# TRF_PCB_021726.net
KiCad netlist of a schematic drawn in EAGLE
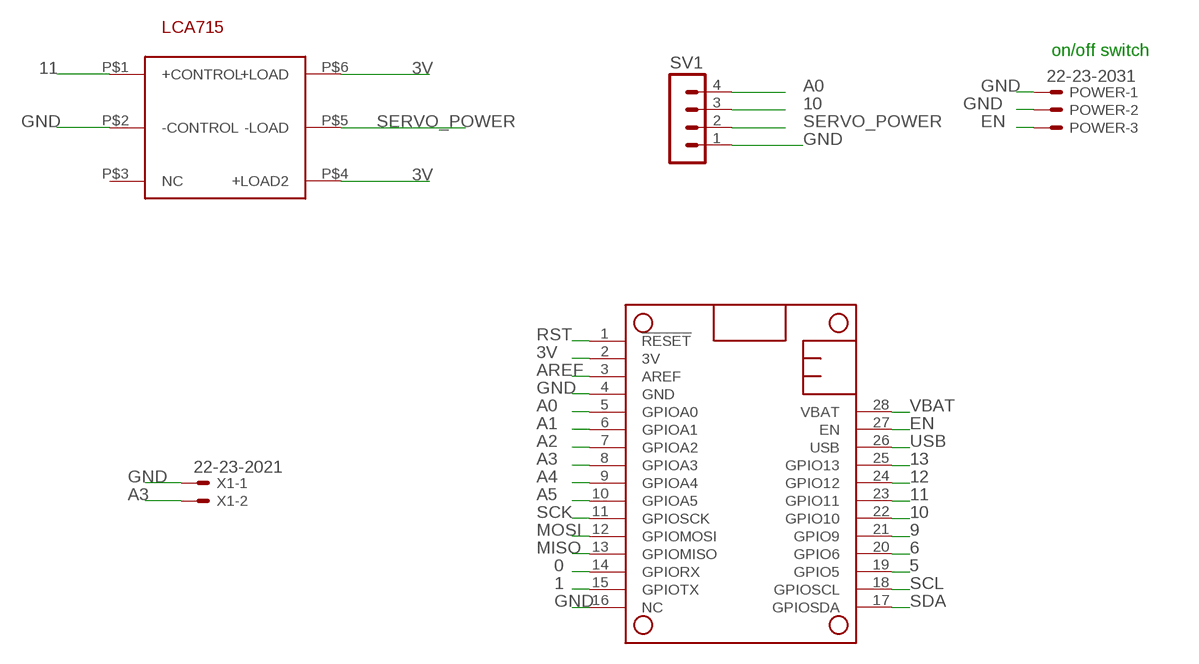
[diagram p0: schematic, sheet 1]

(export (version "E")
  (design (tool "Eeschema 10.0.6"))
  (components
    (comp (ref "MS2")
      (value "MICROSHIELD_NODIM")
      (footprint "eagle-import:MICROSHIELD_DIM")
      (libsource (lib "eagle-import") (part "MICROSHIELD_NODIM"))
    )
    (comp (ref "POWER")
      (value "22-23-2031")
      (footprint "eagle-import:22-23-2031")
      (fields (field (name "MF") "MOLEX"))
      (libsource (lib "eagle-import") (part "22-23-2031"))
    )
    (comp (ref "SSR3")
      (value "LCA715S")
      (footprint "eagle-import:LCA7XX")
      (libsource (lib "eagle-import") (part "LCA715S"))
    )
    (comp (ref "SV1")
      (value "MA04-1")
      (footprint "eagle-import:MA04-1")
      (libsource (lib "eagle-import") (part "MA04-1"))
    )
    (comp (ref "X1")
      (value "22-23-2021")
      (footprint "eagle-import:22-23-2021")
      (fields (field (name "MF") "MOLEX"))
      (libsource (lib "eagle-import") (part "22-23-2021"))
    )
  )
  (nets
    (net (code "1") (name "/0") (class "Default")
      (node (ref "MS2") (pin "14") (pinfunction "GPIORX_14") (pintype "bidirectional"))
    )
    (net (code "2") (name "/1") (class "Default")
      (node (ref "MS2") (pin "15") (pinfunction "GPIOTX_15") (pintype "bidirectional"))
    )
    (net (code "3") (name "/3V") (class "Default")
      (node (ref "MS2") (pin "2") (pinfunction "3V_2") (pintype "power_in"))
      (node (ref "SSR3") (pin "P$4") (pinfunction "+LOAD2_P$4") (pintype "bidirectional"))
      (node (ref "SSR3") (pin "P$6") (pinfunction "+LOAD_P$6") (pintype "bidirectional"))
    )
    (net (code "4") (name "/5") (class "Default")
      (node (ref "MS2") (pin "19") (pinfunction "GPIO5_19") (pintype "bidirectional"))
    )
    (net (code "5") (name "/6") (class "Default")
      (node (ref "MS2") (pin "20") (pinfunction "GPIO6_20") (pintype "bidirectional"))
    )
    (net (code "6") (name "/9") (class "Default")
      (node (ref "MS2") (pin "21") (pinfunction "GPIO9_21") (pintype "bidirectional"))
    )
    (net (code "7") (name "/10") (class "Default")
      (node (ref "MS2") (pin "22") (pinfunction "GPIO10_22") (pintype "bidirectional"))
      (node (ref "SV1") (pin "3") (pinfunction "3_3") (pintype "passive"))
    )
    (net (code "8") (name "/11") (class "Default")
      (node (ref "MS2") (pin "23") (pinfunction "GPIO11_23") (pintype "bidirectional"))
      (node (ref "SSR3") (pin "P$1") (pinfunction "+CONTROL_P$1") (pintype "bidirectional"))
    )
    (net (code "9") (name "/12") (class "Default")
      (node (ref "MS2") (pin "24") (pinfunction "GPIO12_24") (pintype "bidirectional"))
    )
    (net (code "10") (name "/13") (class "Default")
      (node (ref "MS2") (pin "25") (pinfunction "GPIO13_25") (pintype "bidirectional"))
    )
    (net (code "11") (name "/A0") (class "Default")
      (node (ref "MS2") (pin "5") (pinfunction "GPIOA0_5") (pintype "bidirectional"))
      (node (ref "SV1") (pin "4") (pinfunction "4_4") (pintype "passive"))
    )
    (net (code "12") (name "/A1") (class "Default")
      (node (ref "MS2") (pin "6") (pinfunction "GPIOA1_6") (pintype "bidirectional"))
    )
    (net (code "13") (name "/A2") (class "Default")
      (node (ref "MS2") (pin "7") (pinfunction "GPIOA2_7") (pintype "bidirectional"))
    )
    (net (code "14") (name "/A3") (class "Default")
      (node (ref "MS2") (pin "8") (pinfunction "GPIOA3_8") (pintype "bidirectional"))
      (node (ref "X1") (pin "2") (pinfunction "S_2") (pintype "passive"))
    )
    (net (code "15") (name "/A4") (class "Default")
      (node (ref "MS2") (pin "9") (pinfunction "GPIOA4_9") (pintype "bidirectional"))
    )
    (net (code "16") (name "/A5") (class "Default")
      (node (ref "MS2") (pin "10") (pinfunction "GPIOA5_10") (pintype "bidirectional"))
    )
    (net (code "17") (name "/AREF") (class "Default")
      (node (ref "MS2") (pin "3") (pinfunction "AREF_3") (pintype "passive"))
    )
    (net (code "18") (name "/EN") (class "Default")
      (node (ref "MS2") (pin "27") (pinfunction "EN_27") (pintype "passive"))
      (node (ref "POWER") (pin "3") (pinfunction "S_3") (pintype "passive"))
    )
    (net (code "19") (name "/GND") (class "Default")
      (node (ref "MS2") (pin "16") (pinfunction "NC_16") (pintype "passive"))
      (node (ref "MS2") (pin "4") (pinfunction "GND_4") (pintype "power_in"))
      (node (ref "POWER") (pin "1") (pinfunction "S_1") (pintype "passive"))
      (node (ref "POWER") (pin "2") (pinfunction "S_2") (pintype "passive"))
      (node (ref "SSR3") (pin "P$2") (pinfunction "-CONTROL_P$2") (pintype "bidirectional"))
      (node (ref "SV1") (pin "1") (pinfunction "1_1") (pintype "passive"))
      (node (ref "X1") (pin "1") (pinfunction "S_1") (pintype "passive"))
    )
    (net (code "20") (name "/MISO") (class "Default")
      (node (ref "MS2") (pin "13") (pinfunction "GPIOMISO_13") (pintype "bidirectional"))
    )
    (net (code "21") (name "/MOSI") (class "Default")
      (node (ref "MS2") (pin "12") (pinfunction "GPIOMOSI_12") (pintype "bidirectional"))
    )
    (net (code "22") (name "/RST") (class "Default")
      (node (ref "MS2") (pin "1") (pinfunction "~{RESET}_1") (pintype "input"))
    )
    (net (code "23") (name "/SCK") (class "Default")
      (node (ref "MS2") (pin "11") (pinfunction "GPIOSCK_11") (pintype "bidirectional"))
    )
    (net (code "24") (name "/SCL") (class "Default")
      (node (ref "MS2") (pin "18") (pinfunction "GPIOSCL_18") (pintype "bidirectional"))
    )
    (net (code "25") (name "/SDA") (class "Default")
      (node (ref "MS2") (pin "17") (pinfunction "GPIOSDA_17") (pintype "bidirectional"))
    )
    (net (code "26") (name "/SERVO_POWER") (class "Default")
      (node (ref "SSR3") (pin "P$5") (pinfunction "-LOAD_P$5") (pintype "bidirectional"))
      (node (ref "SV1") (pin "2") (pinfunction "2_2") (pintype "passive"))
    )
    (net (code "27") (name "/USB") (class "Default")
      (node (ref "MS2") (pin "26") (pinfunction "USB_26") (pintype "power_in"))
    )
    (net (code "28") (name "/VBAT") (class "Default")
      (node (ref "MS2") (pin "28") (pinfunction "VBAT_28") (pintype "power_in"))
    )
    (net (code "29") (name "unconnected-(SSR3-NC-PadP$3)") (class "Default")
      (node (ref "SSR3") (pin "P$3") (pinfunction "NC_P$3") (pintype "bidirectional"))
    )
  )
)
